# 2_Green_activation.net
KiCad netlist of a schematic drawn in Altium Designer
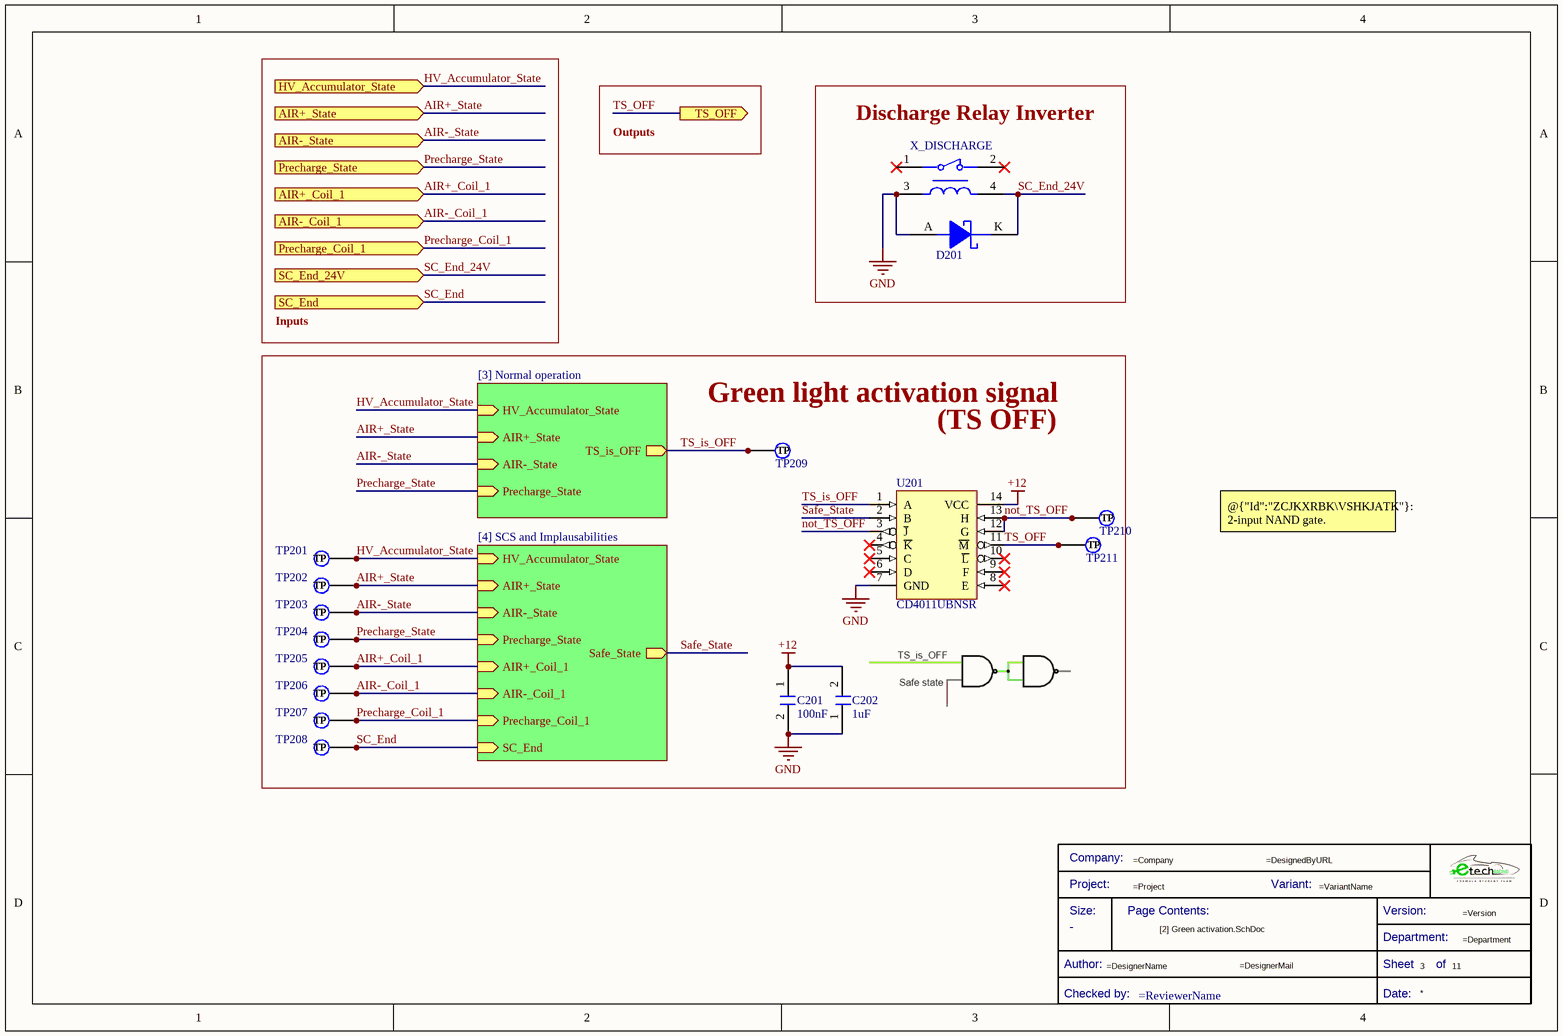
[diagram p0: [2] Green activation.SchDoc]

(export (version "E")
  (design (tool "Eeschema 10.0.6"))
  (components
    (comp (ref "*")
      (value "Title Block_template")
      (description "Standard Title Block")
      (fields
        (field (name "SIZE") "-")
        (field (name ".CREATOR") "GP")
        (field (name ".PCBCHECK") "GP")
        (field (name ".SCHCHECK") "GP")
      )
      (libsource (lib "e-Tech_Racing") (part "Title Block_template"))
    )
    (comp (ref "C201")
      (value "885012207098")
      (footprint "C0805FNPC-R")
      (description "Cap, 0.1ΜF, 50V, 10%, X7R, 0805")
      (fields
        (field (name "TOLERANCE") "10%")
        (field (name "CAPACITANCE") "100nF")
        (field (name ".CREATOR") "DR")
      )
      (libsource (lib "Passives") (part "C100n-50V-0805FNPC-X7R"))
    )
    (comp (ref "C202")
      (value "885012207103")
      (footprint "C0805FNPC-R")
      (fields
        (field (name "TOLERANCE") "10%")
        (field (name "CAPACITANCE") "1uF")
        (field (name ".CREATOR") "GP")
      )
      (libsource (lib "Passives") (part "C1u-50V-0805FNPC-X7R"))
    )
    (comp (ref "D201")
      (value "CMDSH05-4 TR PBFREE")
      (footprint "DSC-0.5/40-SOD_323 - duplicate")
      (description "CMDSH Series 40 V 500 mA Surface Mount Schottky Diode - SOD-323")
      (fields
        (field (name "MANUFACTURER") "Central Semiconductor")
        (field (name "MANUFACTURER PART NUMBER") "CMDSH05-4TR")
        (field (name ".CREATOR") "GP")
      )
      (libsource (lib "Semiconductor") (part "DSC-0.5/40-SOD_323"))
    )
    (comp (ref "TP201")
      (value "TestPoint")
      (footprint "TestPoint")
      (description "Test Point 1x1 mm")
      (fields (field (name ".CREATOR") "GP") (field (name ".PCBCHECK") "GP") (field (name ".SCHCHECK") "GP"))
      (libsource (lib "e-Tech_Racing") (part "TestPoint"))
    )
    (comp (ref "TP202")
      (value "TestPoint")
      (footprint "TestPoint")
      (description "Test Point 1x1 mm")
      (fields (field (name ".CREATOR") "GP") (field (name ".PCBCHECK") "GP") (field (name ".SCHCHECK") "GP"))
      (libsource (lib "e-Tech_Racing") (part "TestPoint"))
    )
    (comp (ref "TP203")
      (value "TestPoint")
      (footprint "TestPoint")
      (description "Test Point 1x1 mm")
      (fields (field (name ".CREATOR") "GP") (field (name ".PCBCHECK") "GP") (field (name ".SCHCHECK") "GP"))
      (libsource (lib "e-Tech_Racing") (part "TestPoint"))
    )
    (comp (ref "TP204")
      (value "TestPoint")
      (footprint "TestPoint")
      (description "Test Point 1x1 mm")
      (fields (field (name ".CREATOR") "GP") (field (name ".PCBCHECK") "GP") (field (name ".SCHCHECK") "GP"))
      (libsource (lib "e-Tech_Racing") (part "TestPoint"))
    )
    (comp (ref "TP205")
      (value "TestPoint")
      (footprint "TestPoint")
      (description "Test Point 1x1 mm")
      (fields (field (name ".CREATOR") "GP") (field (name ".PCBCHECK") "GP") (field (name ".SCHCHECK") "GP"))
      (libsource (lib "e-Tech_Racing") (part "TestPoint"))
    )
    (comp (ref "TP206")
      (value "TestPoint")
      (footprint "TestPoint")
      (description "Test Point 1x1 mm")
      (fields (field (name ".CREATOR") "GP") (field (name ".PCBCHECK") "GP") (field (name ".SCHCHECK") "GP"))
      (libsource (lib "e-Tech_Racing") (part "TestPoint"))
    )
    (comp (ref "TP207")
      (value "TestPoint")
      (footprint "TestPoint")
      (description "Test Point 1x1 mm")
      (fields (field (name ".CREATOR") "GP") (field (name ".PCBCHECK") "GP") (field (name ".SCHCHECK") "GP"))
      (libsource (lib "e-Tech_Racing") (part "TestPoint"))
    )
    (comp (ref "TP208")
      (value "TestPoint")
      (footprint "TestPoint")
      (description "Test Point 1x1 mm")
      (fields (field (name ".CREATOR") "GP") (field (name ".PCBCHECK") "GP") (field (name ".SCHCHECK") "GP"))
      (libsource (lib "e-Tech_Racing") (part "TestPoint"))
    )
    (comp (ref "TP209")
      (value "TestPoint")
      (footprint "TestPoint")
      (description "Test Point 1x1 mm")
      (fields (field (name ".CREATOR") "GP") (field (name ".PCBCHECK") "GP") (field (name ".SCHCHECK") "GP"))
      (libsource (lib "e-Tech_Racing") (part "TestPoint"))
    )
    (comp (ref "TP210")
      (value "TestPoint")
      (footprint "TestPoint")
      (description "Test Point 1x1 mm")
      (fields (field (name ".CREATOR") "GP") (field (name ".PCBCHECK") "GP") (field (name ".SCHCHECK") "GP"))
      (libsource (lib "e-Tech_Racing") (part "TestPoint"))
    )
    (comp (ref "TP211")
      (value "TestPoint")
      (footprint "TestPoint")
      (description "Test Point 1x1 mm")
      (fields (field (name ".CREATOR") "GP") (field (name ".PCBCHECK") "GP") (field (name ".SCHCHECK") "GP"))
      (libsource (lib "e-Tech_Racing") (part "TestPoint"))
    )
    (comp (ref "U201")
      (value "CD4011UBSNR")
      (footprint "ARRAY_4_NAND")
      (description "CD4011UB Cmos Quad 2-INPUT Nand")
      (fields
        (field (name "MANUFACTURER") "Texas Instruments")
        (field (name "MANUFACTURER PART NUMBER") "CD4011UBNSR")
        (field (name ".CREATOR") "DO")
      )
      (libsource (lib "Integrated circuits") (part "Array_4_NAND"))
    )
    (comp (ref "X_DISCHARGE")
      (value "DBR72410FU")
      (footprint "Relay_DAR72410FU")
      (description "Relay, Reed Switch, SPNC, Rhodium Cntcts, 24VDC, 10kV Isol., PCB Mnt/Coil Conn./FL HV")
      (fields (field (name "MANUFACTURER") "Cynergy3") (field (name "MANUFACTURER PART NUMBER") "DBR72410F"))
      (libsource (lib "Electromechanical") (part "Relay_DBR72410FU"))
    )
  )
  (nets
    (net (code "1") (name "+12") (class "Default")
      (node (ref "C201") (pin "1") (pinfunction "1_1") (pintype "passive"))
      (node (ref "C202") (pin "2") (pinfunction "2_2") (pintype "passive"))
      (node (ref "U201") (pin "14") (pinfunction "VCC_14") (pintype "power_in"))
    )
    (net (code "2") (name "/AIR+_Coil_1") (class "Default")
      (node (ref "TP205") (pin "1") (pinfunction "TP_1") (pintype "passive"))
    )
    (net (code "3") (name "/AIR+_State") (class "Default")
      (node (ref "TP202") (pin "1") (pinfunction "TP_1") (pintype "passive"))
    )
    (net (code "4") (name "/AIR-_Coil_1") (class "Default")
      (node (ref "TP206") (pin "1") (pinfunction "TP_1") (pintype "passive"))
    )
    (net (code "5") (name "/AIR-_State") (class "Default")
      (node (ref "TP203") (pin "1") (pinfunction "TP_1") (pintype "passive"))
    )
    (net (code "6") (name "/HV_Accumulator_State") (class "Default")
      (node (ref "TP201") (pin "1") (pinfunction "TP_1") (pintype "passive"))
    )
    (net (code "7") (name "/Precharge_Coil_1") (class "Default")
      (node (ref "TP207") (pin "1") (pinfunction "TP_1") (pintype "passive"))
    )
    (net (code "8") (name "/Precharge_State") (class "Default")
      (node (ref "TP204") (pin "1") (pinfunction "TP_1") (pintype "passive"))
    )
    (net (code "9") (name "/SC_End") (class "Default")
      (node (ref "TP208") (pin "1") (pinfunction "TP_1") (pintype "passive"))
    )
    (net (code "10") (name "/SC_End_24V") (class "Default")
      (node (ref "D201") (pin "K") (pinfunction "K_K") (pintype "passive"))
      (node (ref "X_DISCHARGE") (pin "4") (pinfunction "4_4") (pintype "passive"))
    )
    (net (code "11") (name "/Safe_State") (class "Default")
      (node (ref "U201") (pin "2") (pinfunction "B_2") (pintype "input"))
    )
    (net (code "12") (name "/TS_OFF") (class "Default")
      (node (ref "TP211") (pin "1") (pinfunction "TP_1") (pintype "passive"))
      (node (ref "U201") (pin "11") (pinfunction "~{M}_11") (pintype "output"))
    )
    (net (code "13") (name "/TS_is_OFF") (class "Default")
      (node (ref "TP209") (pin "1") (pinfunction "TP_1") (pintype "passive"))
      (node (ref "U201") (pin "1") (pinfunction "A_1") (pintype "input"))
    )
    (net (code "14") (name "/not_TS_OFF") (class "Default")
      (node (ref "TP210") (pin "1") (pinfunction "TP_1") (pintype "passive"))
      (node (ref "U201") (pin "12") (pinfunction "G_12") (pintype "input"))
      (node (ref "U201") (pin "13") (pinfunction "H_13") (pintype "input"))
      (node (ref "U201") (pin "3") (pinfunction "~{J}_3") (pintype "output"))
    )
    (net (code "15") (name "GND") (class "Default")
      (node (ref "C201") (pin "2") (pinfunction "2_2") (pintype "passive"))
      (node (ref "C202") (pin "1") (pinfunction "1_1") (pintype "passive"))
      (node (ref "D201") (pin "A") (pinfunction "A_A") (pintype "passive"))
      (node (ref "U201") (pin "7") (pinfunction "GND_7") (pintype "power_in"))
      (node (ref "X_DISCHARGE") (pin "3") (pinfunction "3_3") (pintype "passive"))
    )
    (net (code "16") (name "unconnected-(U201-C-Pad5)") (class "Default")
      (node (ref "U201") (pin "5") (pinfunction "C_5") (pintype "input+no_connect"))
    )
    (net (code "17") (name "unconnected-(U201-D-Pad6)") (class "Default")
      (node (ref "U201") (pin "6") (pinfunction "D_6") (pintype "input+no_connect"))
    )
    (net (code "18") (name "unconnected-(U201-E-Pad8)") (class "Default")
      (node (ref "U201") (pin "8") (pinfunction "E_8") (pintype "input+no_connect"))
    )
    (net (code "19") (name "unconnected-(U201-F-Pad9)") (class "Default")
      (node (ref "U201") (pin "9") (pinfunction "F_9") (pintype "input+no_connect"))
    )
    (net (code "20") (name "unconnected-(U201-~{K}-Pad4)") (class "Default")
      (node (ref "U201") (pin "4") (pinfunction "~{K}_4") (pintype "output+no_connect"))
    )
    (net (code "21") (name "unconnected-(U201-~{L}-Pad10)") (class "Default")
      (node (ref "U201") (pin "10") (pinfunction "~{L}_10") (pintype "output+no_connect"))
    )
    (net (code "22") (name "unconnected-(X_DISCHARGE-Pad1)") (class "Default")
      (node (ref "X_DISCHARGE") (pin "1") (pinfunction "1_1") (pintype "passive+no_connect"))
    )
    (net (code "23") (name "unconnected-(X_DISCHARGE-Pad2)") (class "Default")
      (node (ref "X_DISCHARGE") (pin "2") (pinfunction "2_2") (pintype "passive+no_connect"))
    )
  )
)
